# KSS_4_GPS.net
KiCad netlist of a schematic drawn in Altium Designer
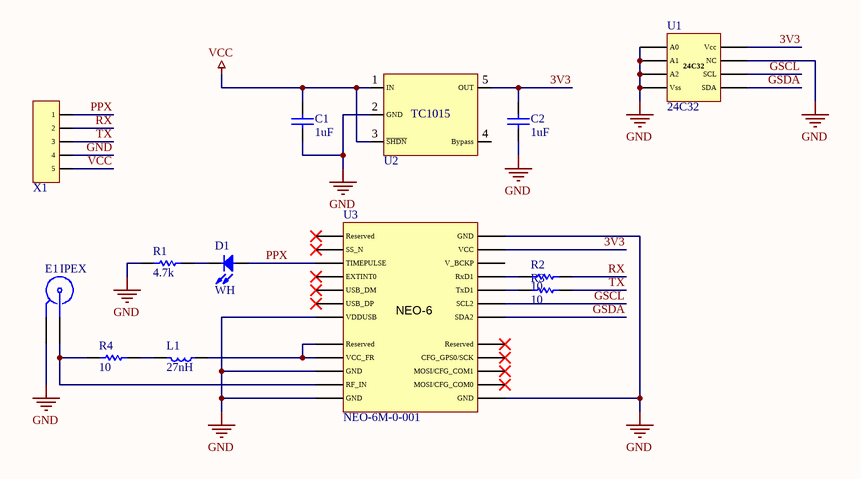
[diagram p0: KSS_4_GPS.SchDoc]

(export (version "E")
  (design (tool "Eeschema 10.0.6"))
  (components
    (comp (ref "C1")
      (value "Capacitor")
      (footprint "CAP_0805")
      (fields (field (name "CAPACITANCE") "1uF"))
      (libsource (lib "COMPONENTS_2022") (part "Capacitor"))
    )
    (comp (ref "C2")
      (value "Capacitor")
      (footprint "CAP_0805")
      (fields (field (name "CAPACITANCE") "1uF"))
      (libsource (lib "COMPONENTS_2022") (part "Capacitor"))
    )
    (comp (ref "D1")
      (value "WH")
      (footprint "LED_0805")
      (libsource (lib "COMPONENTS_2022") (part "Diode LED"))
    )
    (comp (ref "E1") (value "IPEX") (footprint "IPEX") (libsource (lib "COMPONENTS_2022") (part "Antenna")))
    (comp (ref "L1")
      (value "Inductor")
      (footprint "IND_0805")
      (fields (field (name "INDUCTANCE") "27nH"))
      (libsource (lib "COMPONENTS_2022") (part "Inductor"))
    )
    (comp (ref "R1")
      (value "Resistor")
      (footprint "RES_0805")
      (fields (field (name "RESISTANCE") "4.7k"))
      (libsource (lib "COMPONENTS_2022") (part "Resistor"))
    )
    (comp (ref "R2")
      (value "Resistor")
      (footprint "RES_0805")
      (fields (field (name "RESISTANCE") "10"))
      (libsource (lib "COMPONENTS_2022") (part "Resistor"))
    )
    (comp (ref "R3")
      (value "Resistor")
      (footprint "RES_0805")
      (fields (field (name "RESISTANCE") "10"))
      (libsource (lib "COMPONENTS_2022") (part "Resistor"))
    )
    (comp (ref "R4")
      (value "Resistor")
      (footprint "RES_0805")
      (fields (field (name "RESISTANCE") "10"))
      (libsource (lib "COMPONENTS_2022") (part "Resistor"))
    )
    (comp (ref "U1")
      (value "24C32")
      (footprint "TSSOP-8")
      (description "Smart Serial EEPROM I2C")
      (libsource (lib "COMPONENTS_2022") (part "24C32"))
    )
    (comp (ref "U2")
      (value "TC1015")
      (footprint "SOT23_5_PIN")
      (libsource (lib "COMPONENTS_2022") (part "TC1015"))
    )
    (comp (ref "U3")
      (value "NEO-6M-0-001")
      (footprint "NEO-6M-0-001")
      (description "GPS module")
      (libsource (lib "COMPONENTS_2022") (part "NEO-6M-0-001"))
    )
    (comp (ref "X1")
      (value "HEADER_X5")
      (footprint "HEADER_1X5_M")
      (libsource (lib "HEADERS") (part "HEADER_X5"))
    )
  )
  (nets
    (net (code "1") (name "/3V3") (class "Default")
      (node (ref "C2") (pin "1") (pinfunction "1_1") (pintype "passive"))
      (node (ref "U1") (pin "8") (pinfunction "Vcc_8") (pintype "passive"))
      (node (ref "U2") (pin "5") (pinfunction "OUT_5") (pintype "passive"))
      (node (ref "U3") (pin "23") (pinfunction "VCC_23") (pintype "passive"))
    )
    (net (code "2") (name "/GSCL") (class "Default")
      (node (ref "U1") (pin "6") (pinfunction "SCL_6") (pintype "passive"))
      (node (ref "U3") (pin "19") (pinfunction "SCL2_19") (pintype "passive"))
    )
    (net (code "3") (name "/GSDA") (class "Default")
      (node (ref "U1") (pin "5") (pinfunction "SDA_5") (pintype "passive"))
      (node (ref "U3") (pin "18") (pinfunction "SDA2_18") (pintype "passive"))
    )
    (net (code "4") (name "/PPX") (class "Default")
      (node (ref "D1") (pin "1") (pinfunction "A_1") (pintype "passive"))
      (node (ref "U3") (pin "3") (pinfunction "TIMEPULSE_3") (pintype "passive"))
      (node (ref "X1") (pin "1") (pinfunction "1_1") (pintype "passive"))
    )
    (net (code "5") (name "/RX") (class "Default")
      (node (ref "R2") (pin "1") (pinfunction "1_1") (pintype "passive"))
      (node (ref "X1") (pin "2") (pinfunction "2_2") (pintype "passive"))
    )
    (net (code "6") (name "/TX") (class "Default")
      (node (ref "R3") (pin "1") (pinfunction "1_1") (pintype "passive"))
      (node (ref "X1") (pin "3") (pinfunction "3_3") (pintype "passive"))
    )
    (net (code "7") (name "GND") (class "Default")
      (node (ref "C1") (pin "2") (pinfunction "2_2") (pintype "passive"))
      (node (ref "C2") (pin "2") (pinfunction "2_2") (pintype "passive"))
      (node (ref "E1") (pin "2") (pinfunction "2_2") (pintype "passive"))
      (node (ref "R1") (pin "2") (pinfunction "2_2") (pintype "passive"))
      (node (ref "U1") (pin "1") (pinfunction "A0_1") (pintype "passive"))
      (node (ref "U1") (pin "2") (pinfunction "A1_2") (pintype "passive"))
      (node (ref "U1") (pin "3") (pinfunction "A2_3") (pintype "passive"))
      (node (ref "U1") (pin "4") (pinfunction "Vss_4") (pintype "passive"))
      (node (ref "U1") (pin "7") (pinfunction "NC_7") (pintype "passive"))
      (node (ref "U2") (pin "2") (pinfunction "GND_2") (pintype "passive"))
      (node (ref "U3") (pin "10") (pinfunction "GND_10") (pintype "passive"))
      (node (ref "U3") (pin "12") (pinfunction "GND_12") (pintype "passive"))
      (node (ref "U3") (pin "13") (pinfunction "GND_13") (pintype "passive"))
      (node (ref "U3") (pin "24") (pinfunction "GND_24") (pintype "passive"))
      (node (ref "U3") (pin "7") (pinfunction "VDDUSB_7") (pintype "passive"))
      (node (ref "X1") (pin "4") (pinfunction "4_4") (pintype "passive"))
    )
    (net (code "8") (name "Net-(D1-K)") (class "Default")
      (node (ref "D1") (pin "2") (pinfunction "K_2") (pintype "passive"))
      (node (ref "R1") (pin "1") (pinfunction "1_1") (pintype "passive"))
    )
    (net (code "9") (name "Net-(L1-Pad1)") (class "Default")
      (node (ref "L1") (pin "1") (pinfunction "1_1") (pintype "passive"))
      (node (ref "R4") (pin "1") (pinfunction "1_1") (pintype "passive"))
    )
    (net (code "10") (name "Net-(U3-RF_IN)") (class "Default")
      (node (ref "E1") (pin "1") (pinfunction "1_1") (pintype "passive"))
      (node (ref "R4") (pin "2") (pinfunction "2_2") (pintype "passive"))
      (node (ref "U3") (pin "11") (pinfunction "RF_IN_11") (pintype "passive"))
    )
    (net (code "11") (name "Net-(U3-RxD1)") (class "Default")
      (node (ref "R2") (pin "2") (pinfunction "2_2") (pintype "passive"))
      (node (ref "U3") (pin "21") (pinfunction "RxD1_21") (pintype "passive"))
    )
    (net (code "12") (name "Net-(U3-TxD1)") (class "Default")
      (node (ref "R3") (pin "2") (pinfunction "2_2") (pintype "passive"))
      (node (ref "U3") (pin "20") (pinfunction "TxD1_20") (pintype "passive"))
    )
    (net (code "13") (name "Net-(U3-VCC_FR)") (class "Default")
      (node (ref "L1") (pin "2") (pinfunction "2_2") (pintype "passive"))
      (node (ref "U3") (pin "8") (pinfunction "Reserved_8") (pintype "passive"))
      (node (ref "U3") (pin "9") (pinfunction "VCC_FR_9") (pintype "passive"))
    )
    (net (code "14") (name "VCC") (class "Default")
      (node (ref "C1") (pin "1") (pinfunction "1_1") (pintype "passive"))
      (node (ref "U2") (pin "1") (pinfunction "IN_1") (pintype "passive"))
      (node (ref "U2") (pin "3") (pinfunction "~{SHDN}_3") (pintype "passive"))
      (node (ref "X1") (pin "5") (pinfunction "5_5") (pintype "passive"))
    )
    (net (code "15") (name "unconnected-(U2-Bypass-Pad4)") (class "Default")
      (node (ref "U2") (pin "4") (pinfunction "Bypass_4") (pintype "passive"))
    )
    (net (code "16") (name "unconnected-(U3-CFG_GPS0{slash}SCK-Pad16)") (class "Default")
      (node (ref "U3") (pin "16") (pinfunction "CFG_GPS0/SCK_16") (pintype "passive+no_connect"))
    )
    (net (code "17") (name "unconnected-(U3-EXTINT0-Pad4)") (class "Default")
      (node (ref "U3") (pin "4") (pinfunction "EXTINT0_4") (pintype "passive+no_connect"))
    )
    (net (code "18") (name "unconnected-(U3-MOSI{slash}CFG_COM0-Pad14)") (class "Default")
      (node (ref "U3") (pin "14") (pinfunction "MOSI/CFG_COM0_14") (pintype "passive+no_connect"))
    )
    (net (code "19") (name "unconnected-(U3-MOSI{slash}CFG_COM1-Pad15)") (class "Default")
      (node (ref "U3") (pin "15") (pinfunction "MOSI/CFG_COM1_15") (pintype "passive+no_connect"))
    )
    (net (code "20") (name "unconnected-(U3-Reserved-Pad1)") (class "Default")
      (node (ref "U3") (pin "1") (pinfunction "Reserved_1") (pintype "passive+no_connect"))
    )
    (net (code "21") (name "unconnected-(U3-Reserved-Pad17)") (class "Default")
      (node (ref "U3") (pin "17") (pinfunction "Reserved_17") (pintype "passive+no_connect"))
    )
    (net (code "22") (name "unconnected-(U3-SS_N-Pad2)") (class "Default")
      (node (ref "U3") (pin "2") (pinfunction "SS_N_2") (pintype "passive+no_connect"))
    )
    (net (code "23") (name "unconnected-(U3-USB_DM-Pad5)") (class "Default")
      (node (ref "U3") (pin "5") (pinfunction "USB_DM_5") (pintype "passive+no_connect"))
    )
    (net (code "24") (name "unconnected-(U3-USB_DP-Pad6)") (class "Default")
      (node (ref "U3") (pin "6") (pinfunction "USB_DP_6") (pintype "passive+no_connect"))
    )
    (net (code "25") (name "unconnected-(U3-V_BCKP-Pad22)") (class "Default")
      (node (ref "U3") (pin "22") (pinfunction "V_BCKP_22") (pintype "passive"))
    )
  )
)
